# mspfacedraft2.net
KiCad netlist of a schematic drawn in EAGLE
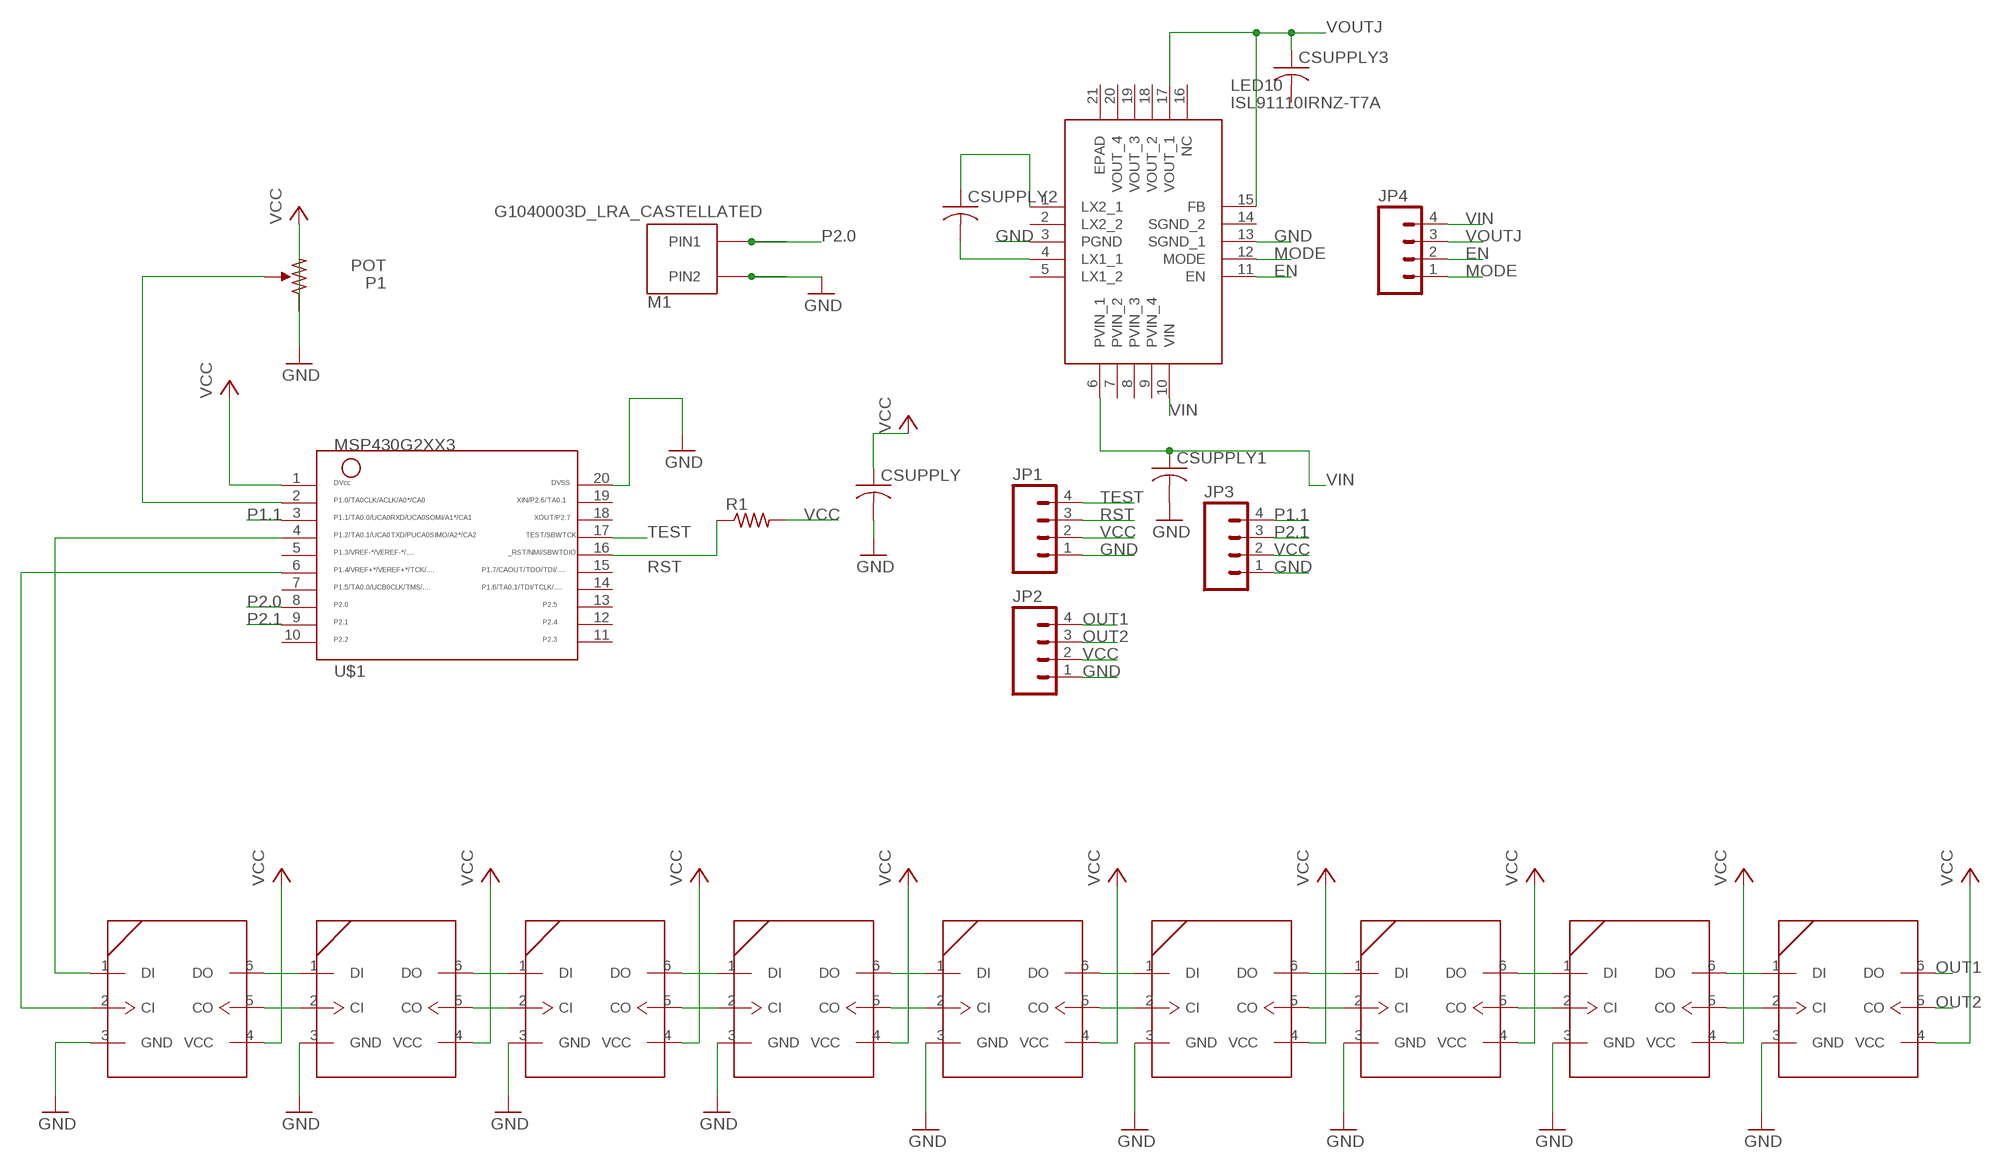
[diagram p0: schematic, sheet 1]

(export (version "E")
  (design (tool "Eeschema 10.0.6"))
  (components
    (comp (ref "CSUPPLY")
      (value "C-USC1206")
      (footprint "eagle-import:C1206")
      (libsource (lib "eagle-import") (part "C-USC1206"))
    )
    (comp (ref "CSUPPLY1")
      (value "C-USC1206")
      (footprint "eagle-import:C1206")
      (libsource (lib "eagle-import") (part "C-USC1206"))
    )
    (comp (ref "CSUPPLY2")
      (value "C-USC1206")
      (footprint "eagle-import:C1206")
      (libsource (lib "eagle-import") (part "C-USC1206"))
    )
    (comp (ref "CSUPPLY3")
      (value "C-USC1206")
      (footprint "eagle-import:C1206")
      (libsource (lib "eagle-import") (part "C-USC1206"))
    )
    (comp (ref "JP1")
      (value "M04LOCK")
      (footprint "eagle-import:1X04_LOCK")
      (libsource (lib "eagle-import") (part "M04LOCK"))
    )
    (comp (ref "JP2")
      (value "M04LOCK")
      (footprint "eagle-import:1X04_LOCK")
      (libsource (lib "eagle-import") (part "M04LOCK"))
    )
    (comp (ref "JP3")
      (value "M04LOCK")
      (footprint "eagle-import:1X04_LOCK")
      (libsource (lib "eagle-import") (part "M04LOCK"))
    )
    (comp (ref "JP4")
      (value "M04LOCK")
      (footprint "eagle-import:1X04_LOCK")
      (libsource (lib "eagle-import") (part "M04LOCK"))
    )
    (comp (ref "LED1")
      (value "APA102")
      (footprint "eagle-import:5050")
      (libsource (lib "eagle-import") (part "APA102"))
    )
    (comp (ref "LED2")
      (value "APA102")
      (footprint "eagle-import:5050")
      (libsource (lib "eagle-import") (part "APA102"))
    )
    (comp (ref "LED3")
      (value "APA102")
      (footprint "eagle-import:5050")
      (libsource (lib "eagle-import") (part "APA102"))
    )
    (comp (ref "LED4")
      (value "APA102")
      (footprint "eagle-import:5050")
      (libsource (lib "eagle-import") (part "APA102"))
    )
    (comp (ref "LED5")
      (value "APA102")
      (footprint "eagle-import:5050")
      (libsource (lib "eagle-import") (part "APA102"))
    )
    (comp (ref "LED6")
      (value "APA102")
      (footprint "eagle-import:5050")
      (libsource (lib "eagle-import") (part "APA102"))
    )
    (comp (ref "LED7")
      (value "APA102")
      (footprint "eagle-import:5050")
      (libsource (lib "eagle-import") (part "APA102"))
    )
    (comp (ref "LED8")
      (value "APA102")
      (footprint "eagle-import:5050")
      (libsource (lib "eagle-import") (part "APA102"))
    )
    (comp (ref "LED9")
      (value "APA102")
      (footprint "eagle-import:5050")
      (libsource (lib "eagle-import") (part "APA102"))
    )
    (comp (ref "LED10")
      (value "ISL91110IRNZ-T7A")
      (footprint "eagle-import:QFN50P400X400X100-21N")
      (fields (field (name "MOUSER_PART_NUMBER") "968-ISL91110IRNZ-T7A"))
      (libsource (lib "eagle-import") (part "ISL91110IRNZ-T7A"))
    )
    (comp (ref "M1")
      (value "G1040003D_LRA_CASTELLATED")
      (footprint "eagle-import:COIN_VIBRATION_MOTOR_CASTEL")
      (libsource (lib "eagle-import") (part "G1040003D_LRA_CASTELLATED"))
    )
    (comp (ref "P1")
      (value "POT")
      (footprint "eagle-import:POT")
      (libsource (lib "eagle-import") (part "POT"))
    )
    (comp (ref "R1")
      (value "R-US_R1206")
      (footprint "eagle-import:R1206")
      (libsource (lib "eagle-import") (part "R-US_R1206"))
    )
    (comp (ref "U$1")
      (value "MSP430G2XX3TSSOP")
      (footprint "eagle-import:PW20")
      (libsource (lib "eagle-import") (part "MSP430G2XX3TSSOP"))
    )
  )
  (nets
    (net (code "1") (name "/EN") (class "Default")
      (node (ref "JP4") (pin "2") (pinfunction "2_2") (pintype "passive"))
      (node (ref "LED10") (pin "11") (pinfunction "EN_11") (pintype "bidirectional"))
    )
    (net (code "2") (name "/MODE") (class "Default")
      (node (ref "JP4") (pin "1") (pinfunction "1_1") (pintype "passive"))
      (node (ref "LED10") (pin "12") (pinfunction "MODE_12") (pintype "bidirectional"))
    )
    (net (code "3") (name "/OUT1") (class "Default")
      (node (ref "JP2") (pin "4") (pinfunction "4_4") (pintype "passive"))
      (node (ref "LED9") (pin "6") (pinfunction "DO_6") (pintype "output"))
    )
    (net (code "4") (name "/OUT2") (class "Default")
      (node (ref "JP2") (pin "3") (pinfunction "3_3") (pintype "passive"))
      (node (ref "LED9") (pin "5") (pinfunction "CO_5") (pintype "output"))
    )
    (net (code "5") (name "/P1.1") (class "Default")
      (node (ref "JP3") (pin "4") (pinfunction "4_4") (pintype "passive"))
      (node (ref "U$1") (pin "3") (pinfunction "3_3") (pintype "bidirectional"))
    )
    (net (code "6") (name "/P2.0") (class "Default")
      (node (ref "M1") (pin "P$1") (pinfunction "PIN1_P$1") (pintype "bidirectional"))
      (node (ref "U$1") (pin "8") (pinfunction "8_8") (pintype "bidirectional"))
    )
    (net (code "7") (name "/P2.1") (class "Default")
      (node (ref "JP3") (pin "3") (pinfunction "3_3") (pintype "passive"))
      (node (ref "U$1") (pin "9") (pinfunction "9_9") (pintype "bidirectional"))
    )
    (net (code "8") (name "/RST") (class "Default")
      (node (ref "JP1") (pin "3") (pinfunction "3_3") (pintype "passive"))
      (node (ref "R1") (pin "1") (pinfunction "1_1") (pintype "passive"))
      (node (ref "U$1") (pin "16") (pinfunction "16_16") (pintype "bidirectional"))
    )
    (net (code "9") (name "/TEST") (class "Default")
      (node (ref "JP1") (pin "4") (pinfunction "4_4") (pintype "passive"))
      (node (ref "U$1") (pin "17") (pinfunction "17_17") (pintype "bidirectional"))
    )
    (net (code "10") (name "/VIN") (class "Default")
      (node (ref "CSUPPLY1") (pin "1") (pinfunction "1_1") (pintype "passive"))
      (node (ref "JP4") (pin "4") (pinfunction "4_4") (pintype "passive"))
      (node (ref "LED10") (pin "10") (pinfunction "VIN_10") (pintype "bidirectional"))
      (node (ref "LED10") (pin "6") (pinfunction "PVIN_1_6") (pintype "bidirectional"))
    )
    (net (code "11") (name "/VOUTJ") (class "Default")
      (node (ref "CSUPPLY3") (pin "1") (pinfunction "1_1") (pintype "passive"))
      (node (ref "JP4") (pin "3") (pinfunction "3_3") (pintype "passive"))
      (node (ref "LED10") (pin "15") (pinfunction "FB_15") (pintype "bidirectional"))
      (node (ref "LED10") (pin "17") (pinfunction "VOUT_1_17") (pintype "bidirectional"))
    )
    (net (code "12") (name "GND") (class "Default")
      (node (ref "CSUPPLY") (pin "2") (pinfunction "2_2") (pintype "passive"))
      (node (ref "CSUPPLY1") (pin "2") (pinfunction "2_2") (pintype "passive"))
      (node (ref "JP1") (pin "1") (pinfunction "1_1") (pintype "passive"))
      (node (ref "JP2") (pin "1") (pinfunction "1_1") (pintype "passive"))
      (node (ref "JP3") (pin "1") (pinfunction "1_1") (pintype "passive"))
      (node (ref "LED1") (pin "3") (pinfunction "GND_3") (pintype "power_in"))
      (node (ref "LED10") (pin "13") (pinfunction "SGND_1_13") (pintype "bidirectional"))
      (node (ref "LED10") (pin "3") (pinfunction "PGND_3") (pintype "bidirectional"))
      (node (ref "LED2") (pin "3") (pinfunction "GND_3") (pintype "power_in"))
      (node (ref "LED3") (pin "3") (pinfunction "GND_3") (pintype "power_in"))
      (node (ref "LED4") (pin "3") (pinfunction "GND_3") (pintype "power_in"))
      (node (ref "LED5") (pin "3") (pinfunction "GND_3") (pintype "power_in"))
      (node (ref "LED6") (pin "3") (pinfunction "GND_3") (pintype "power_in"))
      (node (ref "LED7") (pin "3") (pinfunction "GND_3") (pintype "power_in"))
      (node (ref "LED8") (pin "3") (pinfunction "GND_3") (pintype "power_in"))
      (node (ref "LED9") (pin "3") (pinfunction "GND_3") (pintype "power_in"))
      (node (ref "M1") (pin "P$2") (pinfunction "PIN2_P$2") (pintype "bidirectional"))
      (node (ref "P1") (pin "GND") (pinfunction "CW_GND") (pintype "passive"))
      (node (ref "U$1") (pin "20") (pinfunction "20_20") (pintype "bidirectional"))
    )
    (net (code "13") (name "Net-(LED1-CI)") (class "Default")
      (node (ref "LED1") (pin "2") (pinfunction "CI_2") (pintype "input"))
      (node (ref "U$1") (pin "6") (pinfunction "6_6") (pintype "bidirectional"))
    )
    (net (code "14") (name "Net-(LED1-CO)") (class "Default")
      (node (ref "LED1") (pin "5") (pinfunction "CO_5") (pintype "output"))
      (node (ref "LED2") (pin "2") (pinfunction "CI_2") (pintype "input"))
    )
    (net (code "15") (name "Net-(LED1-DI)") (class "Default")
      (node (ref "LED1") (pin "1") (pinfunction "DI_1") (pintype "input"))
      (node (ref "U$1") (pin "4") (pinfunction "4_4") (pintype "bidirectional"))
    )
    (net (code "16") (name "Net-(LED1-DO)") (class "Default")
      (node (ref "LED1") (pin "6") (pinfunction "DO_6") (pintype "output"))
      (node (ref "LED2") (pin "1") (pinfunction "DI_1") (pintype "input"))
    )
    (net (code "17") (name "Net-(LED2-CO)") (class "Default")
      (node (ref "LED2") (pin "5") (pinfunction "CO_5") (pintype "output"))
      (node (ref "LED3") (pin "2") (pinfunction "CI_2") (pintype "input"))
    )
    (net (code "18") (name "Net-(LED2-DO)") (class "Default")
      (node (ref "LED2") (pin "6") (pinfunction "DO_6") (pintype "output"))
      (node (ref "LED3") (pin "1") (pinfunction "DI_1") (pintype "input"))
    )
    (net (code "19") (name "Net-(LED3-CO)") (class "Default")
      (node (ref "LED3") (pin "5") (pinfunction "CO_5") (pintype "output"))
      (node (ref "LED4") (pin "2") (pinfunction "CI_2") (pintype "input"))
    )
    (net (code "20") (name "Net-(LED3-DO)") (class "Default")
      (node (ref "LED3") (pin "6") (pinfunction "DO_6") (pintype "output"))
      (node (ref "LED4") (pin "1") (pinfunction "DI_1") (pintype "input"))
    )
    (net (code "21") (name "Net-(LED4-CO)") (class "Default")
      (node (ref "LED4") (pin "5") (pinfunction "CO_5") (pintype "output"))
      (node (ref "LED5") (pin "2") (pinfunction "CI_2") (pintype "input"))
    )
    (net (code "22") (name "Net-(LED4-DO)") (class "Default")
      (node (ref "LED4") (pin "6") (pinfunction "DO_6") (pintype "output"))
      (node (ref "LED5") (pin "1") (pinfunction "DI_1") (pintype "input"))
    )
    (net (code "23") (name "Net-(LED5-CO)") (class "Default")
      (node (ref "LED5") (pin "5") (pinfunction "CO_5") (pintype "output"))
      (node (ref "LED6") (pin "2") (pinfunction "CI_2") (pintype "input"))
    )
    (net (code "24") (name "Net-(LED5-DO)") (class "Default")
      (node (ref "LED5") (pin "6") (pinfunction "DO_6") (pintype "output"))
      (node (ref "LED6") (pin "1") (pinfunction "DI_1") (pintype "input"))
    )
    (net (code "25") (name "Net-(LED6-CO)") (class "Default")
      (node (ref "LED6") (pin "5") (pinfunction "CO_5") (pintype "output"))
      (node (ref "LED7") (pin "2") (pinfunction "CI_2") (pintype "input"))
    )
    (net (code "26") (name "Net-(LED6-DO)") (class "Default")
      (node (ref "LED6") (pin "6") (pinfunction "DO_6") (pintype "output"))
      (node (ref "LED7") (pin "1") (pinfunction "DI_1") (pintype "input"))
    )
    (net (code "27") (name "Net-(LED7-CO)") (class "Default")
      (node (ref "LED7") (pin "5") (pinfunction "CO_5") (pintype "output"))
      (node (ref "LED8") (pin "2") (pinfunction "CI_2") (pintype "input"))
    )
    (net (code "28") (name "Net-(LED7-DO)") (class "Default")
      (node (ref "LED7") (pin "6") (pinfunction "DO_6") (pintype "output"))
      (node (ref "LED8") (pin "1") (pinfunction "DI_1") (pintype "input"))
    )
    (net (code "29") (name "Net-(LED8-CO)") (class "Default")
      (node (ref "LED8") (pin "5") (pinfunction "CO_5") (pintype "output"))
      (node (ref "LED9") (pin "2") (pinfunction "CI_2") (pintype "input"))
    )
    (net (code "30") (name "Net-(LED8-DO)") (class "Default")
      (node (ref "LED8") (pin "6") (pinfunction "DO_6") (pintype "output"))
      (node (ref "LED9") (pin "1") (pinfunction "DI_1") (pintype "input"))
    )
    (net (code "31") (name "Net-(LED10-LX1_1)") (class "Default")
      (node (ref "CSUPPLY2") (pin "2") (pinfunction "2_2") (pintype "passive"))
      (node (ref "LED10") (pin "4") (pinfunction "LX1_1_4") (pintype "bidirectional"))
    )
    (net (code "32") (name "Net-(LED10-LX2_1)") (class "Default")
      (node (ref "CSUPPLY2") (pin "1") (pinfunction "1_1") (pintype "passive"))
      (node (ref "LED10") (pin "1") (pinfunction "LX2_1_1") (pintype "bidirectional"))
    )
    (net (code "33") (name "Net-(P1-S)") (class "Default")
      (node (ref "P1") (pin "SIG") (pinfunction "S_SIG") (pintype "bidirectional"))
      (node (ref "U$1") (pin "2") (pinfunction "2_2") (pintype "bidirectional"))
    )
    (net (code "34") (name "VCC") (class "Default")
      (node (ref "CSUPPLY") (pin "1") (pinfunction "1_1") (pintype "passive"))
      (node (ref "JP1") (pin "2") (pinfunction "2_2") (pintype "passive"))
      (node (ref "JP2") (pin "2") (pinfunction "2_2") (pintype "passive"))
      (node (ref "JP3") (pin "2") (pinfunction "2_2") (pintype "passive"))
      (node (ref "LED1") (pin "4") (pinfunction "VCC_4") (pintype "power_in"))
      (node (ref "LED2") (pin "4") (pinfunction "VCC_4") (pintype "power_in"))
      (node (ref "LED3") (pin "4") (pinfunction "VCC_4") (pintype "power_in"))
      (node (ref "LED4") (pin "4") (pinfunction "VCC_4") (pintype "power_in"))
      (node (ref "LED5") (pin "4") (pinfunction "VCC_4") (pintype "power_in"))
      (node (ref "LED6") (pin "4") (pinfunction "VCC_4") (pintype "power_in"))
      (node (ref "LED7") (pin "4") (pinfunction "VCC_4") (pintype "power_in"))
      (node (ref "LED8") (pin "4") (pinfunction "VCC_4") (pintype "power_in"))
      (node (ref "LED9") (pin "4") (pinfunction "VCC_4") (pintype "power_in"))
      (node (ref "P1") (pin "VDD") (pinfunction "CCW_VDD") (pintype "passive"))
      (node (ref "R1") (pin "2") (pinfunction "2_2") (pintype "passive"))
      (node (ref "U$1") (pin "1") (pinfunction "1_1") (pintype "bidirectional"))
    )
    (net (code "35") (name "unconnected-(CSUPPLY3-Pad2)") (class "Default")
      (node (ref "CSUPPLY3") (pin "2") (pinfunction "2_2") (pintype "passive"))
    )
    (net (code "36") (name "unconnected-(LED10-EPAD-Pad21)") (class "Default")
      (node (ref "LED10") (pin "21") (pinfunction "EPAD_21") (pintype "bidirectional"))
    )
    (net (code "37") (name "unconnected-(LED10-LX1_2-Pad5)") (class "Default")
      (node (ref "LED10") (pin "5") (pinfunction "LX1_2_5") (pintype "bidirectional"))
    )
    (net (code "38") (name "unconnected-(LED10-LX2_2-Pad2)") (class "Default")
      (node (ref "LED10") (pin "2") (pinfunction "LX2_2_2") (pintype "bidirectional"))
    )
    (net (code "39") (name "unconnected-(LED10-NC-Pad16)") (class "Default")
      (node (ref "LED10") (pin "16") (pinfunction "NC_16") (pintype "no_connect"))
    )
    (net (code "40") (name "unconnected-(LED10-PVIN_2-Pad7)") (class "Default")
      (node (ref "LED10") (pin "7") (pinfunction "PVIN_2_7") (pintype "bidirectional"))
    )
    (net (code "41") (name "unconnected-(LED10-PVIN_3-Pad8)") (class "Default")
      (node (ref "LED10") (pin "8") (pinfunction "PVIN_3_8") (pintype "bidirectional"))
    )
    (net (code "42") (name "unconnected-(LED10-PVIN_4-Pad9)") (class "Default")
      (node (ref "LED10") (pin "9") (pinfunction "PVIN_4_9") (pintype "bidirectional"))
    )
    (net (code "43") (name "unconnected-(LED10-SGND_2-Pad14)") (class "Default")
      (node (ref "LED10") (pin "14") (pinfunction "SGND_2_14") (pintype "bidirectional"))
    )
    (net (code "44") (name "unconnected-(LED10-VOUT_2-Pad18)") (class "Default")
      (node (ref "LED10") (pin "18") (pinfunction "VOUT_2_18") (pintype "bidirectional"))
    )
    (net (code "45") (name "unconnected-(LED10-VOUT_3-Pad19)") (class "Default")
      (node (ref "LED10") (pin "19") (pinfunction "VOUT_3_19") (pintype "bidirectional"))
    )
    (net (code "46") (name "unconnected-(LED10-VOUT_4-Pad20)") (class "Default")
      (node (ref "LED10") (pin "20") (pinfunction "VOUT_4_20") (pintype "bidirectional"))
    )
    (net (code "47") (name "unconnected-(U$1-Pad5)") (class "Default")
      (node (ref "U$1") (pin "5") (pinfunction "5_5") (pintype "bidirectional"))
    )
    (net (code "48") (name "unconnected-(U$1-Pad7)") (class "Default")
      (node (ref "U$1") (pin "7") (pinfunction "7_7") (pintype "bidirectional"))
    )
    (net (code "49") (name "unconnected-(U$1-Pad10)") (class "Default")
      (node (ref "U$1") (pin "10") (pinfunction "10_10") (pintype "bidirectional"))
    )
    (net (code "50") (name "unconnected-(U$1-Pad11)") (class "Default")
      (node (ref "U$1") (pin "11") (pinfunction "11_11") (pintype "bidirectional"))
    )
    (net (code "51") (name "unconnected-(U$1-Pad12)") (class "Default")
      (node (ref "U$1") (pin "12") (pinfunction "12_12") (pintype "bidirectional"))
    )
    (net (code "52") (name "unconnected-(U$1-Pad13)") (class "Default")
      (node (ref "U$1") (pin "13") (pinfunction "13_13") (pintype "bidirectional"))
    )
    (net (code "53") (name "unconnected-(U$1-Pad14)") (class "Default")
      (node (ref "U$1") (pin "14") (pinfunction "14_14") (pintype "bidirectional"))
    )
    (net (code "54") (name "unconnected-(U$1-Pad15)") (class "Default")
      (node (ref "U$1") (pin "15") (pinfunction "15_15") (pintype "bidirectional"))
    )
    (net (code "55") (name "unconnected-(U$1-Pad18)") (class "Default")
      (node (ref "U$1") (pin "18") (pinfunction "18_18") (pintype "bidirectional"))
    )
    (net (code "56") (name "unconnected-(U$1-Pad19)") (class "Default")
      (node (ref "U$1") (pin "19") (pinfunction "19_19") (pintype "bidirectional"))
    )
  )
)
